# Power_Supply.net
KiCad netlist of a schematic drawn in Altium Designer
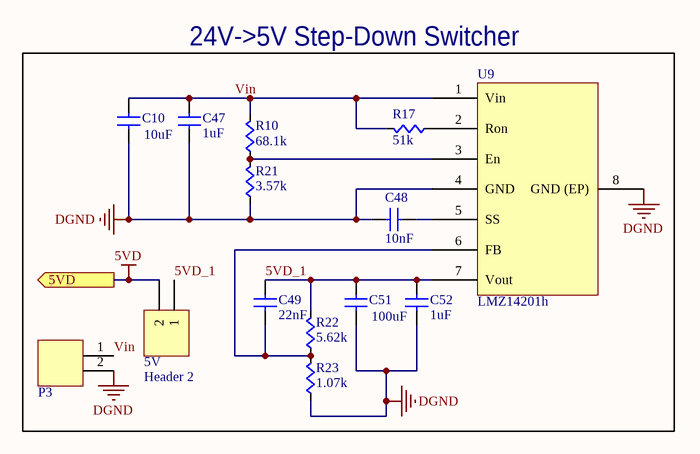
[diagram p0: Power_Supply.SchDoc]

(export (version "E")
  (design (tool "Eeschema 10.0.6"))
  (components
    (comp (ref "5V")
      (value "Header 2")
      (footprint "HDR1X2")
      (description "Header, 2-Pin")
      (fields (field (name "PUBLISHER") "Altium Limited"))
      (libsource (lib "Miscellaneous Connectors") (part "Header 2"))
    )
    (comp (ref "C10")
      (value "10uF")
      (footprint "CAP1210")
      (description "CAP CER 10UF 50V 20% X5R 1210")
      (fields (field (name "Comment") "CAP1210"))
      (libsource (lib "SubjuGator8") (part "CAP1210"))
    )
    (comp (ref "C47")
      (value "1uF")
      (footprint "CAP1206")
      (description "CAP CER 1UF 50V 10% X7R 1206")
      (fields (field (name "Comment") "Cap1206"))
      (libsource (lib "Passives") (part "Cap1206"))
    )
    (comp (ref "C48")
      (value "10nF")
      (footprint "CAPC0603")
      (fields (field (name "Comment") "Cap"))
      (libsource (lib "SubjuGator8") (part "Cap"))
    )
    (comp (ref "C49")
      (value "22nF")
      (footprint "CAPC0603")
      (fields (field (name "Comment") "Cap"))
      (libsource (lib "SubjuGator8") (part "Cap"))
    )
    (comp (ref "C51")
      (value "100uF")
      (footprint "CAP1210")
      (description "CAP CER 10UF 50V 20% X5R 1210")
      (fields (field (name "Comment") "CAP1210"))
      (libsource (lib "SubjuGator8") (part "CAP1210"))
    )
    (comp (ref "C52")
      (value "1uF")
      (footprint "CAP1206")
      (description "CAP CER 1UF 50V 10% X7R 1206")
      (fields (field (name "Comment") "Cap1206"))
      (libsource (lib "Passives") (part "Cap1206"))
    )
    (comp (ref "P3")
      (value "2-pin Horz Sherlock")
      (footprint "MOLEX-HDR-1X2-SHERLOCK-HORZ")
      (fields
        (field (name "MANUFACTURER PART NUMBER") "0353630260")
        (field (name "MANUFACTURER") "Molex Inc")
      )
      (libsource (lib "SubjuGator8") (part "MOLEX-HDR-1x2-SHERLOCK_RA"))
    )
    (comp (ref "R10")
      (value "68.1k")
      (footprint "RES0603")
      (fields (field (name "Comment") "Res"))
      (libsource (lib "SubjuGator8") (part "Res"))
    )
    (comp (ref "R17")
      (value "51k")
      (footprint "RES0603")
      (fields (field (name "Comment") "Res"))
      (libsource (lib "SubjuGator8") (part "Res"))
    )
    (comp (ref "R21")
      (value "3.57k")
      (footprint "RES0603")
      (fields (field (name "Comment") "Res"))
      (libsource (lib "SubjuGator8") (part "Res"))
    )
    (comp (ref "R22")
      (value "5.62k")
      (footprint "RES0603")
      (fields (field (name "Comment") "Res"))
      (libsource (lib "SubjuGator8") (part "Res"))
    )
    (comp (ref "R23")
      (value "1.07k")
      (footprint "RES0603")
      (fields (field (name "Comment") "Res"))
      (libsource (lib "SubjuGator8") (part "Res"))
    )
    (comp (ref "U9")
      (value "LMZ14201h")
      (footprint "TO-PMOD-7")
      (description "IC BUCK SYNC ADJ 1A TO-PMOD-7")
      (libsource (lib "ICs") (part "LMZ14201h"))
    )
  )
  (nets
    (net (code "1") (name "/5VD_1") (class "Default")
      (node (ref "5V") (pin "1") (pinfunction "1_1") (pintype "passive"))
      (node (ref "C49") (pin "2") (pinfunction "B_2") (pintype "passive"))
      (node (ref "C51") (pin "1") (pinfunction "A_1") (pintype "passive"))
      (node (ref "C52") (pin "1") (pinfunction "A_1") (pintype "passive"))
      (node (ref "R22") (pin "1") (pinfunction "A_1") (pintype "passive"))
      (node (ref "U9") (pin "7") (pinfunction "Vout_7") (pintype "passive"))
    )
    (net (code "2") (name "/Vin") (class "Default")
      (node (ref "C10") (pin "1") (pinfunction "A_1") (pintype "passive"))
      (node (ref "C47") (pin "1") (pinfunction "A_1") (pintype "passive"))
      (node (ref "P3") (pin "1") (pinfunction "1_1") (pintype "passive"))
      (node (ref "R10") (pin "1") (pinfunction "A_1") (pintype "passive"))
      (node (ref "R17") (pin "1") (pinfunction "A_1") (pintype "passive"))
      (node (ref "U9") (pin "1") (pinfunction "Vin_1") (pintype "passive"))
    )
    (net (code "3") (name "5VD") (class "Default")
      (node (ref "5V") (pin "2") (pinfunction "2_2") (pintype "passive"))
    )
    (net (code "4") (name "DGND") (class "Default")
      (node (ref "C10") (pin "2") (pinfunction "B_2") (pintype "passive"))
      (node (ref "C47") (pin "2") (pinfunction "B_2") (pintype "passive"))
      (node (ref "C48") (pin "1") (pinfunction "A_1") (pintype "passive"))
      (node (ref "C51") (pin "2") (pinfunction "B_2") (pintype "passive"))
      (node (ref "C52") (pin "2") (pinfunction "B_2") (pintype "passive"))
      (node (ref "P3") (pin "2") (pinfunction "2_2") (pintype "passive"))
      (node (ref "R21") (pin "2") (pinfunction "B_2") (pintype "passive"))
      (node (ref "R23") (pin "2") (pinfunction "B_2") (pintype "passive"))
      (node (ref "U9") (pin "4") (pinfunction "GND_4") (pintype "passive"))
      (node (ref "U9") (pin "8") (pinfunction "GND_(EP)_8") (pintype "passive"))
    )
    (net (code "5") (name "Net-(C48-B)") (class "Default")
      (node (ref "C48") (pin "2") (pinfunction "B_2") (pintype "passive"))
      (node (ref "U9") (pin "5") (pinfunction "SS_5") (pintype "passive"))
    )
    (net (code "6") (name "Net-(C49-A)") (class "Default")
      (node (ref "C49") (pin "1") (pinfunction "A_1") (pintype "passive"))
      (node (ref "R22") (pin "2") (pinfunction "B_2") (pintype "passive"))
      (node (ref "R23") (pin "1") (pinfunction "A_1") (pintype "passive"))
      (node (ref "U9") (pin "6") (pinfunction "FB_6") (pintype "passive"))
    )
    (net (code "7") (name "Net-(R10-B)") (class "Default")
      (node (ref "R10") (pin "2") (pinfunction "B_2") (pintype "passive"))
      (node (ref "R21") (pin "1") (pinfunction "A_1") (pintype "passive"))
      (node (ref "U9") (pin "3") (pinfunction "En_3") (pintype "passive"))
    )
    (net (code "8") (name "Net-(R17-B)") (class "Default")
      (node (ref "R17") (pin "2") (pinfunction "B_2") (pintype "passive"))
      (node (ref "U9") (pin "2") (pinfunction "Ron_2") (pintype "passive"))
    )
  )
)
